# detachable-esp8266-4x-wire-to-board.net
KiCad netlist of a schematic drawn in EAGLE
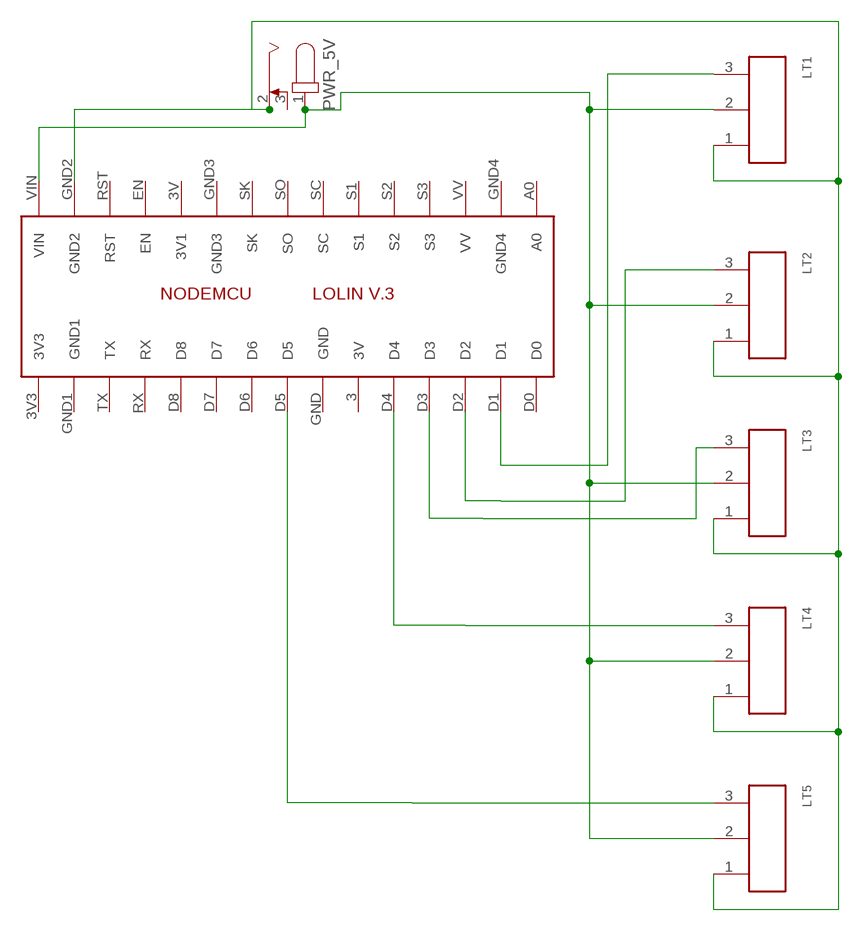
[diagram p0: schematic, sheet 1]

(export (version "E")
  (design (tool "Eeschema 10.0.6"))
  (components
    (comp (ref "IC1")
      (value "LOLINV3SMALL")
      (footprint "eagle-import:LOLINV3_SMALL")
      (libsource (lib "eagle-import") (part "LOLINV3SMALL"))
    )
    (comp (ref "LT1")
      (value "61900311121")
      (footprint "eagle-import:61900311121")
      (libsource (lib "eagle-import") (part "61900311121"))
    )
    (comp (ref "LT2")
      (value "61900311121")
      (footprint "eagle-import:61900311121")
      (libsource (lib "eagle-import") (part "61900311121"))
    )
    (comp (ref "LT3")
      (value "61900311121")
      (footprint "eagle-import:61900311121")
      (libsource (lib "eagle-import") (part "61900311121"))
    )
    (comp (ref "LT4")
      (value "61900311121")
      (footprint "eagle-import:61900311121")
      (libsource (lib "eagle-import") (part "61900311121"))
    )
    (comp (ref "LT5")
      (value "61900311121")
      (footprint "eagle-import:61900311121")
      (libsource (lib "eagle-import") (part "61900311121"))
    )
    (comp (ref "PWR_5V")
      (value "694103303002")
      (footprint "eagle-import:69410X303002")
      (libsource (lib "eagle-import") (part "694103303002"))
    )
  )
  (nets
    (net (code "1") (name "Net-(IC1-PadD1)") (class "Default")
      (node (ref "IC1") (pin "D1") (pinfunction "D1_D1") (pintype "bidirectional"))
      (node (ref "LT1") (pin "3") (pinfunction "3_3") (pintype "passive"))
    )
    (net (code "2") (name "Net-(IC1-PadD2)") (class "Default")
      (node (ref "IC1") (pin "D2") (pinfunction "D2_D2") (pintype "bidirectional"))
      (node (ref "LT2") (pin "3") (pinfunction "3_3") (pintype "passive"))
    )
    (net (code "3") (name "Net-(IC1-PadD3)") (class "Default")
      (node (ref "IC1") (pin "D3") (pinfunction "D3_D3") (pintype "bidirectional"))
      (node (ref "LT3") (pin "3") (pinfunction "3_3") (pintype "passive"))
    )
    (net (code "4") (name "Net-(IC1-PadD4)") (class "Default")
      (node (ref "IC1") (pin "D4") (pinfunction "D4_D4") (pintype "bidirectional"))
      (node (ref "LT4") (pin "3") (pinfunction "3_3") (pintype "passive"))
    )
    (net (code "5") (name "Net-(IC1-PadD5)") (class "Default")
      (node (ref "IC1") (pin "D5") (pinfunction "D5_D5") (pintype "bidirectional"))
      (node (ref "LT5") (pin "3") (pinfunction "3_3") (pintype "passive"))
    )
    (net (code "6") (name "Net-(IC1-PadGND2)") (class "Default")
      (node (ref "IC1") (pin "GND2") (pinfunction "GND2_GND2") (pintype "bidirectional"))
      (node (ref "LT1") (pin "1") (pinfunction "1_1") (pintype "passive"))
      (node (ref "LT2") (pin "1") (pinfunction "1_1") (pintype "passive"))
      (node (ref "LT3") (pin "1") (pinfunction "1_1") (pintype "passive"))
      (node (ref "LT4") (pin "1") (pinfunction "1_1") (pintype "passive"))
      (node (ref "LT5") (pin "1") (pinfunction "1_1") (pintype "passive"))
      (node (ref "PWR_5V") (pin "2") (pinfunction "2_2") (pintype "passive"))
    )
    (net (code "7") (name "Net-(IC1-PadVIN)") (class "Default")
      (node (ref "IC1") (pin "VIN") (pinfunction "VIN_VIN") (pintype "bidirectional"))
      (node (ref "LT1") (pin "2") (pinfunction "2_2") (pintype "passive"))
      (node (ref "LT2") (pin "2") (pinfunction "2_2") (pintype "passive"))
      (node (ref "LT3") (pin "2") (pinfunction "2_2") (pintype "passive"))
      (node (ref "LT4") (pin "2") (pinfunction "2_2") (pintype "passive"))
      (node (ref "LT5") (pin "2") (pinfunction "2_2") (pintype "passive"))
      (node (ref "PWR_5V") (pin "1") (pinfunction "1_1") (pintype "passive"))
    )
    (net (code "8") (name "unconnected-(IC1-3V-Pad3)") (class "Default")
      (node (ref "IC1") (pin "3") (pinfunction "3V_3") (pintype "bidirectional"))
    )
    (net (code "9") (name "unconnected-(IC1-3V1-Pad3V)") (class "Default")
      (node (ref "IC1") (pin "3V") (pinfunction "3V1_3V") (pintype "bidirectional"))
    )
    (net (code "10") (name "unconnected-(IC1-Pad3V3)") (class "Default")
      (node (ref "IC1") (pin "3V3") (pinfunction "3V3_3V3") (pintype "bidirectional"))
    )
    (net (code "11") (name "unconnected-(IC1-PadA0)") (class "Default")
      (node (ref "IC1") (pin "A0") (pinfunction "A0_A0") (pintype "bidirectional"))
    )
    (net (code "12") (name "unconnected-(IC1-PadD0)") (class "Default")
      (node (ref "IC1") (pin "D0") (pinfunction "D0_D0") (pintype "bidirectional"))
    )
    (net (code "13") (name "unconnected-(IC1-PadD6)") (class "Default")
      (node (ref "IC1") (pin "D6") (pinfunction "D6_D6") (pintype "bidirectional"))
    )
    (net (code "14") (name "unconnected-(IC1-PadD7)") (class "Default")
      (node (ref "IC1") (pin "D7") (pinfunction "D7_D7") (pintype "bidirectional"))
    )
    (net (code "15") (name "unconnected-(IC1-PadD8)") (class "Default")
      (node (ref "IC1") (pin "D8") (pinfunction "D8_D8") (pintype "bidirectional"))
    )
    (net (code "16") (name "unconnected-(IC1-PadEN)") (class "Default")
      (node (ref "IC1") (pin "EN") (pinfunction "EN_EN") (pintype "bidirectional"))
    )
    (net (code "17") (name "unconnected-(IC1-PadGND)") (class "Default")
      (node (ref "IC1") (pin "GND") (pinfunction "GND_GND") (pintype "bidirectional"))
    )
    (net (code "18") (name "unconnected-(IC1-PadGND1)") (class "Default")
      (node (ref "IC1") (pin "GND1") (pinfunction "GND1_GND1") (pintype "bidirectional"))
    )
    (net (code "19") (name "unconnected-(IC1-PadGND3)") (class "Default")
      (node (ref "IC1") (pin "GND3") (pinfunction "GND3_GND3") (pintype "bidirectional"))
    )
    (net (code "20") (name "unconnected-(IC1-PadGND4)") (class "Default")
      (node (ref "IC1") (pin "GND4") (pinfunction "GND4_GND4") (pintype "bidirectional"))
    )
    (net (code "21") (name "unconnected-(IC1-PadRST)") (class "Default")
      (node (ref "IC1") (pin "RST") (pinfunction "RST_RST") (pintype "bidirectional"))
    )
    (net (code "22") (name "unconnected-(IC1-PadRX)") (class "Default")
      (node (ref "IC1") (pin "RX") (pinfunction "RX_RX") (pintype "bidirectional"))
    )
    (net (code "23") (name "unconnected-(IC1-PadS1)") (class "Default")
      (node (ref "IC1") (pin "S1") (pinfunction "S1_S1") (pintype "bidirectional"))
    )
    (net (code "24") (name "unconnected-(IC1-PadS2)") (class "Default")
      (node (ref "IC1") (pin "S2") (pinfunction "S2_S2") (pintype "bidirectional"))
    )
    (net (code "25") (name "unconnected-(IC1-PadS3)") (class "Default")
      (node (ref "IC1") (pin "S3") (pinfunction "S3_S3") (pintype "bidirectional"))
    )
    (net (code "26") (name "unconnected-(IC1-PadSC)") (class "Default")
      (node (ref "IC1") (pin "SC") (pinfunction "SC_SC") (pintype "bidirectional"))
    )
    (net (code "27") (name "unconnected-(IC1-PadSK)") (class "Default")
      (node (ref "IC1") (pin "SK") (pinfunction "SK_SK") (pintype "bidirectional"))
    )
    (net (code "28") (name "unconnected-(IC1-PadSO)") (class "Default")
      (node (ref "IC1") (pin "SO") (pinfunction "SO_SO") (pintype "bidirectional"))
    )
    (net (code "29") (name "unconnected-(IC1-PadTX)") (class "Default")
      (node (ref "IC1") (pin "TX") (pinfunction "TX_TX") (pintype "bidirectional"))
    )
    (net (code "30") (name "unconnected-(IC1-PadVV)") (class "Default")
      (node (ref "IC1") (pin "VV") (pinfunction "VV_VV") (pintype "bidirectional"))
    )
    (net (code "31") (name "unconnected-(PWR_5V-Pad3)") (class "Default")
      (node (ref "PWR_5V") (pin "3") (pinfunction "3_3") (pintype "passive"))
    )
  )
)
